# LCD_Screen.net
KiCad netlist of a schematic drawn in Altium Designer
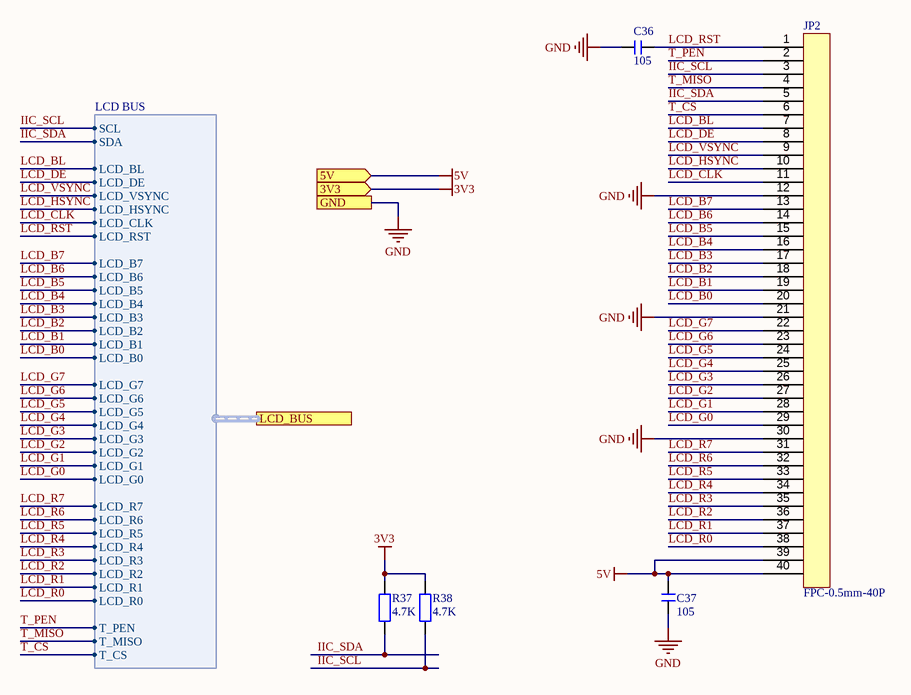
[diagram p0: LCD_Screen.SchDoc]

(export (version "E")
  (design (tool "Eeschema 10.0.6"))
  (components
    (comp (ref "C36")
      (value "105")
      (footprint "C 0603_L")
      (description "贴片电容")
      (libsource (lib "0.1 - 电阻-电容-电感") (part "C"))
    )
    (comp (ref "C37")
      (value "105")
      (footprint "C 0603_L")
      (description "贴片电容")
      (libsource (lib "0.1 - 电阻-电容-电感") (part "C"))
    )
    (comp (ref "JP2")
      (value "FPC-0.5mm-40P")
      (footprint "FPC0.5 2H-WS-40P")
      (description "FPC Connector 0.5mm 40PIN")
      (libsource (lib "CustomizedComponents") (part "FPC-0.5mm-40P"))
    )
    (comp (ref "R37")
      (value "4.7K")
      (footprint "R 0603_L")
      (description "贴片电阻")
      (fields (field (name "版权归属") "来自淘宝 ID：黄晶宝石"))
      (libsource (lib "0.1 - 电阻-电容-电感") (part "R"))
    )
    (comp (ref "R38")
      (value "4.7K")
      (footprint "R 0603_L")
      (description "贴片电阻")
      (fields (field (name "版权归属") "来自淘宝 ID：黄晶宝石"))
      (libsource (lib "0.1 - 电阻-电容-电感") (part "R"))
    )
  )
  (nets
    (net (code "3") (name "/IIC_SCL") (class "Default")
      (node (ref "JP2") (pin "3") (pintype "passive"))
      (node (ref "R38") (pin "1") (pinfunction "1_1") (pintype "passive"))
    )
    (net (code "4") (name "/IIC_SDA") (class "Default")
      (node (ref "JP2") (pin "5") (pintype "passive"))
      (node (ref "R37") (pin "1") (pinfunction "1_1") (pintype "passive"))
    )
    (net (code "5") (name "/LCD_B0") (class "Default") (node (ref "JP2") (pin "20") (pintype "passive")))
    (net (code "6") (name "/LCD_B1") (class "Default") (node (ref "JP2") (pin "19") (pintype "passive")))
    (net (code "7") (name "/LCD_B2") (class "Default") (node (ref "JP2") (pin "18") (pintype "passive")))
    (net (code "8") (name "/LCD_B3") (class "Default") (node (ref "JP2") (pin "17") (pintype "passive")))
    (net (code "9") (name "/LCD_B4") (class "Default") (node (ref "JP2") (pin "16") (pintype "passive")))
    (net (code "10") (name "/LCD_B5") (class "Default") (node (ref "JP2") (pin "15") (pintype "passive")))
    (net (code "11") (name "/LCD_B6") (class "Default") (node (ref "JP2") (pin "14") (pintype "passive")))
    (net (code "12") (name "/LCD_B7") (class "Default") (node (ref "JP2") (pin "13") (pintype "passive")))
    (net (code "13") (name "/LCD_BL") (class "Default") (node (ref "JP2") (pin "7") (pintype "passive")))
    (net (code "14") (name "/LCD_CLK") (class "Default") (node (ref "JP2") (pin "11") (pintype "passive")))
    (net (code "15") (name "/LCD_DE") (class "Default") (node (ref "JP2") (pin "8") (pintype "passive")))
    (net (code "16") (name "/LCD_G0") (class "Default") (node (ref "JP2") (pin "29") (pintype "passive")))
    (net (code "17") (name "/LCD_G1") (class "Default") (node (ref "JP2") (pin "28") (pintype "passive")))
    (net (code "18") (name "/LCD_G2") (class "Default") (node (ref "JP2") (pin "27") (pintype "passive")))
    (net (code "19") (name "/LCD_G3") (class "Default") (node (ref "JP2") (pin "26") (pintype "passive")))
    (net (code "20") (name "/LCD_G4") (class "Default") (node (ref "JP2") (pin "25") (pintype "passive")))
    (net (code "21") (name "/LCD_G5") (class "Default") (node (ref "JP2") (pin "24") (pintype "passive")))
    (net (code "22") (name "/LCD_G6") (class "Default") (node (ref "JP2") (pin "23") (pintype "passive")))
    (net (code "23") (name "/LCD_G7") (class "Default") (node (ref "JP2") (pin "22") (pintype "passive")))
    (net (code "24") (name "/LCD_HSYNC") (class "Default") (node (ref "JP2") (pin "10") (pintype "passive")))
    (net (code "25") (name "/LCD_R0") (class "Default") (node (ref "JP2") (pin "38") (pintype "passive")))
    (net (code "26") (name "/LCD_R1") (class "Default") (node (ref "JP2") (pin "37") (pintype "passive")))
    (net (code "27") (name "/LCD_R2") (class "Default") (node (ref "JP2") (pin "36") (pintype "passive")))
    (net (code "28") (name "/LCD_R3") (class "Default") (node (ref "JP2") (pin "35") (pintype "passive")))
    (net (code "29") (name "/LCD_R4") (class "Default") (node (ref "JP2") (pin "34") (pintype "passive")))
    (net (code "30") (name "/LCD_R5") (class "Default") (node (ref "JP2") (pin "33") (pintype "passive")))
    (net (code "31") (name "/LCD_R6") (class "Default") (node (ref "JP2") (pin "32") (pintype "passive")))
    (net (code "32") (name "/LCD_R7") (class "Default") (node (ref "JP2") (pin "31") (pintype "passive")))
    (net (code "33") (name "/LCD_RST") (class "Default")
      (node (ref "C36") (pin "1") (pinfunction "1_1") (pintype "passive"))
      (node (ref "JP2") (pin "1") (pintype "passive"))
    )
    (net (code "34") (name "/LCD_VSYNC") (class "Default") (node (ref "JP2") (pin "9") (pintype "passive")))
    (net (code "35") (name "/T_CS") (class "Default") (node (ref "JP2") (pin "6") (pintype "passive")))
    (net (code "36") (name "/T_MISO") (class "Default") (node (ref "JP2") (pin "4") (pintype "passive")))
    (net (code "37") (name "/T_PEN") (class "Default") (node (ref "JP2") (pin "2") (pintype "passive")))
    (net (code "39") (name "3V3") (class "Default")
      (node (ref "R37") (pin "2") (pinfunction "2_2") (pintype "passive"))
      (node (ref "R38") (pin "2") (pinfunction "2_2") (pintype "passive"))
    )
    (net (code "40") (name "5V") (class "Default")
      (node (ref "C37") (pin "2") (pinfunction "2_2") (pintype "passive"))
      (node (ref "JP2") (pin "39") (pintype "passive"))
      (node (ref "JP2") (pin "40") (pintype "passive"))
    )
    (net (code "41") (name "GND") (class "Default")
      (node (ref "C36") (pin "2") (pinfunction "2_2") (pintype "passive"))
      (node (ref "C37") (pin "1") (pinfunction "1_1") (pintype "passive"))
      (node (ref "JP2") (pin "12") (pintype "passive"))
      (node (ref "JP2") (pin "21") (pintype "passive"))
      (node (ref "JP2") (pin "30") (pintype "passive"))
    )
  )
)
